# lm78xx_vreg.net
KiCad netlist of a schematic drawn in EAGLE
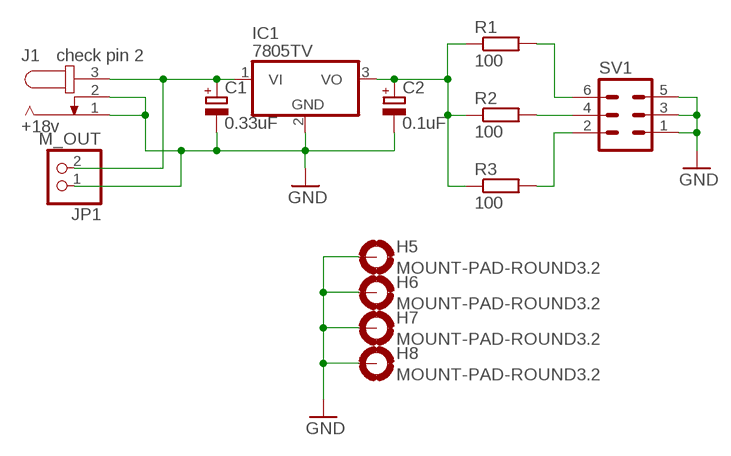
[diagram p0: schematic, sheet 1]

(export (version "E")
  (design (tool "Eeschema 10.0.6"))
  (components
    (comp (ref "C1")
      (value "0.33uF")
      (footprint "eagle-import:E2,5-7")
      (libsource (lib "eagle-import") (part "CPOL-EUE2.5-7"))
    )
    (comp (ref "C2")
      (value "0.1uF")
      (footprint "eagle-import:E2,5-7")
      (libsource (lib "eagle-import") (part "CPOL-EUE2.5-7"))
    )
    (comp (ref "H5")
      (value "MOUNT-PAD-ROUND3.2")
      (footprint "eagle-import:3,2-PAD")
      (libsource (lib "eagle-import") (part "MOUNT-PAD-ROUND3.2"))
    )
    (comp (ref "H6")
      (value "MOUNT-PAD-ROUND3.2")
      (footprint "eagle-import:3,2-PAD")
      (libsource (lib "eagle-import") (part "MOUNT-PAD-ROUND3.2"))
    )
    (comp (ref "H7")
      (value "MOUNT-PAD-ROUND3.2")
      (footprint "eagle-import:3,2-PAD")
      (libsource (lib "eagle-import") (part "MOUNT-PAD-ROUND3.2"))
    )
    (comp (ref "H8")
      (value "MOUNT-PAD-ROUND3.2")
      (footprint "eagle-import:3,2-PAD")
      (libsource (lib "eagle-import") (part "MOUNT-PAD-ROUND3.2"))
    )
    (comp (ref "IC1")
      (value "7805TV")
      (footprint "eagle-import:TO220V")
      (libsource (lib "eagle-import") (part "78TV05"))
    )
    (comp (ref "J1")
      (value "+18v")
      (footprint "eagle-import:SPC4078")
      (libsource (lib "eagle-import") (part "JACK-PLUG1"))
    )
    (comp (ref "JP1")
      (value "M_OUT")
      (footprint "eagle-import:1X02")
      (libsource (lib "eagle-import") (part "PINHD-1X2"))
    )
    (comp (ref "R1")
      (value "100")
      (footprint "eagle-import:R0805W")
      (libsource (lib "eagle-import") (part "R-EU_R0805W"))
    )
    (comp (ref "R2")
      (value "100")
      (footprint "eagle-import:R0805W")
      (libsource (lib "eagle-import") (part "R-EU_R0805W"))
    )
    (comp (ref "R3")
      (value "100")
      (footprint "eagle-import:R0805W")
      (libsource (lib "eagle-import") (part "R-EU_R0805W"))
    )
    (comp (ref "SV1")
      (value "MA03-2")
      (footprint "eagle-import:MA03-2")
      (libsource (lib "eagle-import") (part "MA03-2"))
    )
  )
  (nets
    (net (code "1") (name "GND") (class "Default")
      (node (ref "C1") (pin "-") (pinfunction "-_-") (pintype "passive"))
      (node (ref "C2") (pin "-") (pinfunction "-_-") (pintype "passive"))
      (node (ref "H5") (pin "B3,2") (pinfunction "MOUNT_B3,2") (pintype "passive"))
      (node (ref "H6") (pin "B3,2") (pinfunction "MOUNT_B3,2") (pintype "passive"))
      (node (ref "H7") (pin "B3,2") (pinfunction "MOUNT_B3,2") (pintype "passive"))
      (node (ref "H8") (pin "B3,2") (pinfunction "MOUNT_B3,2") (pintype "passive"))
      (node (ref "IC1") (pin "2") (pinfunction "GND_2") (pintype "passive"))
      (node (ref "J1") (pin "1") (pinfunction "1_1") (pintype "passive"))
      (node (ref "J1") (pin "2") (pinfunction "2_2") (pintype "passive"))
      (node (ref "JP1") (pin "1") (pinfunction "1_1") (pintype "passive"))
      (node (ref "SV1") (pin "1") (pinfunction "1_1") (pintype "passive"))
      (node (ref "SV1") (pin "3") (pinfunction "3_3") (pintype "passive"))
      (node (ref "SV1") (pin "5") (pinfunction "5_5") (pintype "passive"))
    )
    (net (code "2") (name "Net-(IC1-VI)") (class "Default")
      (node (ref "C1") (pin "+") (pinfunction "+_+") (pintype "passive"))
      (node (ref "IC1") (pin "1") (pinfunction "VI_1") (pintype "input"))
      (node (ref "J1") (pin "3") (pinfunction "3_3") (pintype "passive"))
      (node (ref "JP1") (pin "2") (pinfunction "2_2") (pintype "passive"))
    )
    (net (code "3") (name "Net-(IC1-VO)") (class "Default")
      (node (ref "C2") (pin "+") (pinfunction "+_+") (pintype "passive"))
      (node (ref "IC1") (pin "3") (pinfunction "VO_3") (pintype "passive"))
      (node (ref "R1") (pin "1") (pinfunction "1_1") (pintype "passive"))
      (node (ref "R2") (pin "1") (pinfunction "1_1") (pintype "passive"))
      (node (ref "R3") (pin "1") (pinfunction "1_1") (pintype "passive"))
    )
    (net (code "4") (name "Net-(R1-Pad2)") (class "Default")
      (node (ref "R1") (pin "2") (pinfunction "2_2") (pintype "passive"))
      (node (ref "SV1") (pin "6") (pinfunction "6_6") (pintype "passive"))
    )
    (net (code "5") (name "Net-(R2-Pad2)") (class "Default")
      (node (ref "R2") (pin "2") (pinfunction "2_2") (pintype "passive"))
      (node (ref "SV1") (pin "4") (pinfunction "4_4") (pintype "passive"))
    )
    (net (code "6") (name "Net-(R3-Pad2)") (class "Default")
      (node (ref "R3") (pin "2") (pinfunction "2_2") (pintype "passive"))
      (node (ref "SV1") (pin "2") (pinfunction "2_2") (pintype "passive"))
    )
  )
)
